# Power.net
KiCad netlist of a schematic drawn in Altium Designer
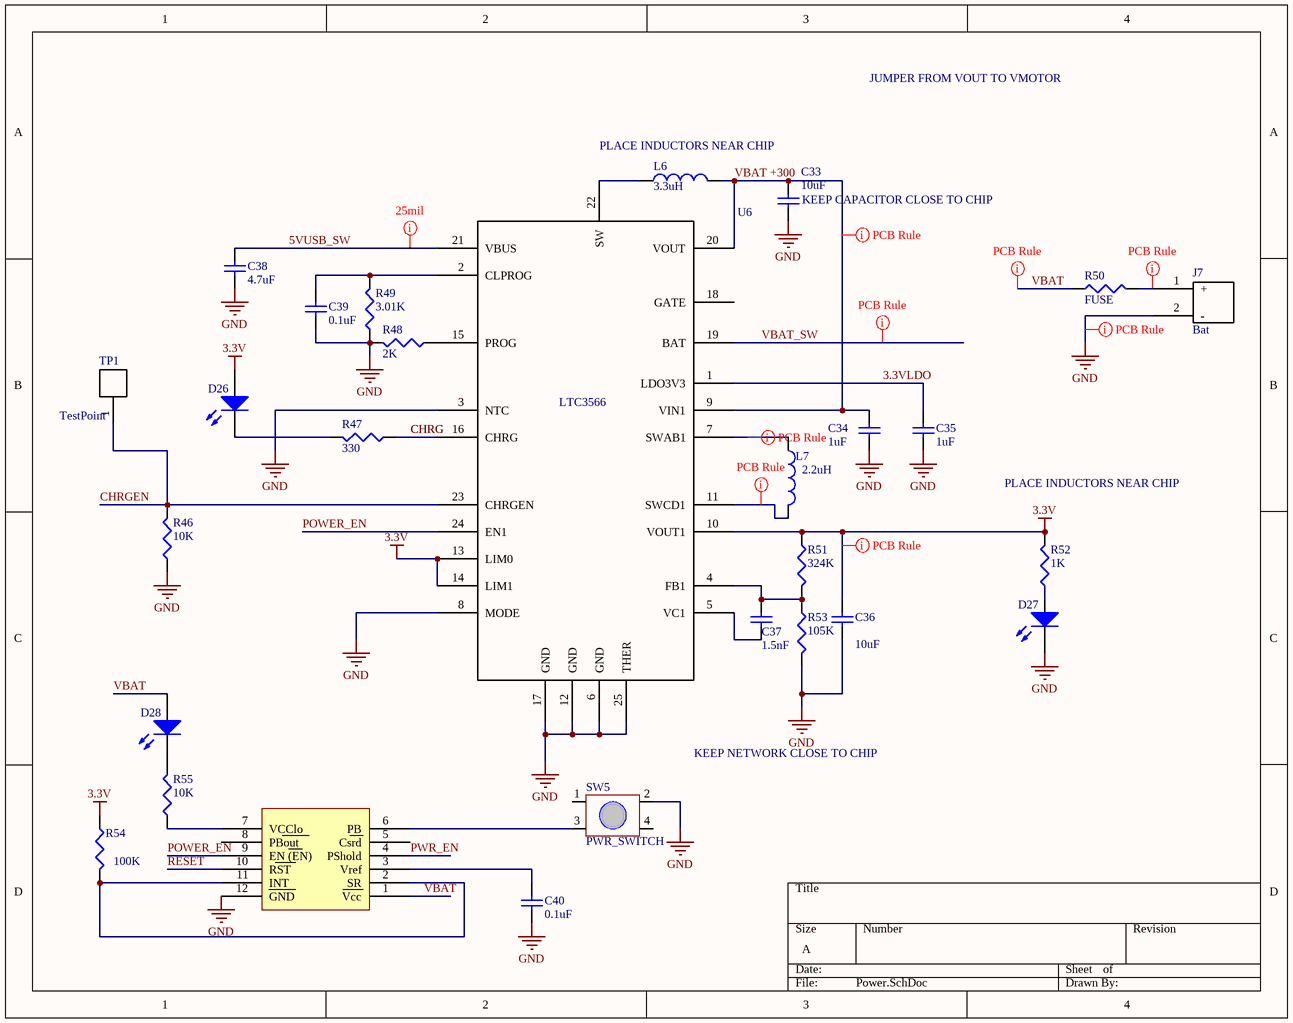
[diagram p0: Power.SchDoc]

(export (version "E")
  (design (tool "Eeschema 10.0.6"))
  (components
    (comp (ref "C33")
      (value "10uF")
      (footprint "CAPC1608L")
      (description "Capacitor")
      (fields (field (name "Comment") "Cap") (field (name "PUBLISHER") "Altium Limited"))
      (libsource (lib "Miscellaneous Devices") (part "Cap"))
    )
    (comp (ref "C34")
      (value "1uF")
      (footprint "CAPC1608L")
      (description "Capacitor")
      (fields (field (name "Comment") "Cap") (field (name "PUBLISHER") "Altium Limited"))
      (libsource (lib "Miscellaneous Devices") (part "Cap"))
    )
    (comp (ref "C35")
      (value "1uF")
      (footprint "CAPC1608L")
      (description "Capacitor")
      (fields (field (name "Comment") "Cap") (field (name "PUBLISHER") "Altium Limited"))
      (libsource (lib "Miscellaneous Devices") (part "Cap"))
    )
    (comp (ref "C36")
      (value "10uF")
      (footprint "CAPC1608L")
      (description "Capacitor")
      (fields (field (name "Comment") "Cap") (field (name "PUBLISHER") "Altium Limited"))
      (libsource (lib "Miscellaneous Devices") (part "Cap"))
    )
    (comp (ref "C37")
      (value "1.5nF")
      (footprint "CAPC1005L")
      (description "Capacitor")
      (fields (field (name "Comment") "Cap") (field (name "PUBLISHER") "Altium Limited"))
      (libsource (lib "Miscellaneous Devices") (part "Cap"))
    )
    (comp (ref "C38")
      (value "4.7uF")
      (footprint "CAPC1608L")
      (description "Capacitor")
      (fields (field (name "Comment") "Cap") (field (name "PUBLISHER") "Altium Limited"))
      (libsource (lib "Miscellaneous Devices") (part "Cap"))
    )
    (comp (ref "C39")
      (value "0.1uF")
      (footprint "CAPC1005L")
      (description "Capacitor")
      (fields (field (name "Comment") "Cap") (field (name "PUBLISHER") "Altium Limited"))
      (libsource (lib "Miscellaneous Devices") (part "Cap"))
    )
    (comp (ref "C40")
      (value "0.1uF")
      (footprint "CAPC1608L")
      (description "Capacitor")
      (fields (field (name "Comment") "Cap") (field (name "PUBLISHER") "Altium Limited"))
      (libsource (lib "Miscellaneous Devices") (part "Cap"))
    )
    (comp (ref "D26")
      (value "Charge")
      (footprint "INDC2012L")
      (description "Typical RED, GREEN, YELLOW, AMBER GaAs LED")
      (fields (field (name "PUBLISHER") "Altium Limited"))
      (libsource (lib "Miscellaneous Devices") (part "LED2"))
    )
    (comp (ref "D27")
      (value "Power")
      (footprint "INDC2012L")
      (description "Typical RED, GREEN, YELLOW, AMBER GaAs LED")
      (fields (field (name "PUBLISHER") "Altium Limited"))
      (libsource (lib "Miscellaneous Devices") (part "LED2"))
    )
    (comp (ref "D28")
      (value "Charge")
      (footprint "INDC2012L")
      (description "Typical RED, GREEN, YELLOW, AMBER GaAs LED")
      (fields (field (name "PUBLISHER") "Altium Limited"))
      (libsource (lib "Miscellaneous Devices") (part "LED2"))
    )
    (comp (ref "J7")
      (value "Bat")
      (footprint "BatteryConnJST")
      (libsource (lib "mrone") (part "BatteryConnJST"))
    )
    (comp (ref "L6") (value "3.3uH") (footprint "IndPow") (libsource (lib "mrone") (part "Inductor")))
    (comp (ref "L7") (value "2.2uH") (footprint "IndPow") (libsource (lib "mrone") (part "Inductor")))
    (comp (ref "R46")
      (value "10K")
      (footprint "RESC1608L")
      (description "Resistor")
      (fields (field (name "Comment") "Res3") (field (name "PUBLISHER") "Altium Limited"))
      (libsource (lib "Miscellaneous Devices") (part "Res3"))
    )
    (comp (ref "R47")
      (value "330")
      (footprint "RESC1608L")
      (description "Resistor")
      (fields (field (name "Comment") "Res3") (field (name "PUBLISHER") "Altium Limited"))
      (libsource (lib "Miscellaneous Devices") (part "Res3"))
    )
    (comp (ref "R48")
      (value "2K")
      (footprint "RESC1608L")
      (description "Resistor")
      (fields (field (name "Comment") "Res3") (field (name "PUBLISHER") "Altium Limited"))
      (libsource (lib "Miscellaneous Devices") (part "Res3"))
    )
    (comp (ref "R49")
      (value "3.01K")
      (footprint "RESC1608L")
      (description "Resistor")
      (fields (field (name "Comment") "Res3") (field (name "PUBLISHER") "Altium Limited"))
      (libsource (lib "Miscellaneous Devices") (part "Res3"))
    )
    (comp (ref "R50")
      (value "FUSE")
      (footprint "RESC3225L")
      (description "Resistor")
      (fields (field (name "Comment") "Res3") (field (name "PUBLISHER") "Altium Limited"))
      (libsource (lib "Miscellaneous Devices") (part "Res3"))
    )
    (comp (ref "R51")
      (value "324K")
      (footprint "RESC1608L")
      (description "Resistor")
      (fields (field (name "Comment") "Res3") (field (name "PUBLISHER") "Altium Limited"))
      (libsource (lib "Miscellaneous Devices") (part "Res3"))
    )
    (comp (ref "R52")
      (value "1K")
      (footprint "RESC1608L")
      (description "Resistor")
      (fields (field (name "Comment") "Res3") (field (name "PUBLISHER") "Altium Limited"))
      (libsource (lib "Miscellaneous Devices") (part "Res3"))
    )
    (comp (ref "R53")
      (value "105K")
      (footprint "RESC1608L")
      (description "Resistor")
      (fields (field (name "Comment") "Res3") (field (name "PUBLISHER") "Altium Limited"))
      (libsource (lib "Miscellaneous Devices") (part "Res3"))
    )
    (comp (ref "R54")
      (value "100K")
      (footprint "RESC1608L")
      (description "Resistor")
      (fields (field (name "Comment") "Res3") (field (name "PUBLISHER") "Altium Limited"))
      (libsource (lib "Miscellaneous Devices") (part "Res3"))
    )
    (comp (ref "R55")
      (value "10K")
      (footprint "RESC1608L")
      (description "Resistor")
      (fields (field (name "Comment") "Res3") (field (name "PUBLISHER") "Altium Limited"))
      (libsource (lib "Miscellaneous Devices") (part "Res3"))
    )
    (comp (ref "SW5")
      (value "PWR_SWITCH")
      (footprint "SwitchTall-TL330")
      (libsource (lib "mrone") (part "Switch-TL330"))
    )
    (comp (ref "TP1")
      (value "TestPoint")
      (footprint "TestPoint")
      (libsource (lib "mrone") (part "TestPoint"))
    )
    (comp (ref "U6")
      (value "LTC3566")
      (footprint "QFN-24")
      (libsource (lib "Schematic Components") (part "LTC3566"))
    )
    (comp (ref "U7") (value "STM6601") (footprint "TDFN12") (libsource (lib "mrone") (part "STM6601")))
  )
  (nets
    (net (code "1") (name "/3.3VLDO") (class "Default")
      (node (ref "C35") (pin "1") (pinfunction "1_1") (pintype "passive"))
      (node (ref "U6") (pin "1") (pinfunction "LDO3V3_1") (pintype "passive"))
    )
    (net (code "2") (name "/5VUSB_SW") (class "Default")
      (node (ref "C38") (pin "2") (pinfunction "2_2") (pintype "passive"))
      (node (ref "U6") (pin "21") (pinfunction "VBUS_21") (pintype "passive"))
    )
    (net (code "3") (name "/CHRG") (class "Default")
      (node (ref "R47") (pin "1") (pinfunction "1_1") (pintype "passive"))
      (node (ref "U6") (pin "16") (pinfunction "CHRG_16") (pintype "passive"))
    )
    (net (code "4") (name "/CHRGEN") (class "Default")
      (node (ref "R46") (pin "2") (pinfunction "2_2") (pintype "passive"))
      (node (ref "TP1") (pin "1") (pintype "passive"))
      (node (ref "U6") (pin "23") (pinfunction "CHRGEN_23") (pintype "passive"))
    )
    (net (code "5") (name "/POWER_EN") (class "Default")
      (node (ref "U6") (pin "24") (pinfunction "EN1_24") (pintype "passive"))
      (node (ref "U7") (pin "9") (pinfunction "EN_(EN)_9") (pintype "passive"))
    )
    (net (code "6") (name "/PWR_EN") (class "Default")
      (node (ref "U7") (pin "4") (pinfunction "PShold_4") (pintype "passive"))
    )
    (net (code "7") (name "/RESET") (class "Default")
      (node (ref "U7") (pin "10") (pinfunction "RST_10") (pintype "passive"))
    )
    (net (code "8") (name "/VBAT") (class "Default")
      (node (ref "D28") (pin "1") (pinfunction "A_1") (pintype "passive"))
      (node (ref "R50") (pin "1") (pinfunction "1_1") (pintype "passive"))
      (node (ref "U7") (pin "1") (pinfunction "Vcc_1") (pintype "open_collector"))
    )
    (net (code "9") (name "/VBAT +300") (class "Default")
      (node (ref "C33") (pin "2") (pinfunction "2_2") (pintype "passive"))
      (node (ref "C34") (pin "1") (pinfunction "1_1") (pintype "passive"))
      (node (ref "L6") (pin "2") (pinfunction "2_2") (pintype "passive"))
      (node (ref "U6") (pin "20") (pinfunction "VOUT_20") (pintype "passive"))
      (node (ref "U6") (pin "9") (pinfunction "VIN1_9") (pintype "passive"))
    )
    (net (code "10") (name "/VBAT_SW") (class "Default")
      (node (ref "U6") (pin "19") (pinfunction "BAT_19") (pintype "passive"))
    )
    (net (code "11") (name "3.3V") (class "Default")
      (node (ref "C36") (pin "2") (pinfunction "2_2") (pintype "passive"))
      (node (ref "D26") (pin "1") (pinfunction "A_1") (pintype "passive"))
      (node (ref "R51") (pin "1") (pinfunction "1_1") (pintype "passive"))
      (node (ref "R52") (pin "2") (pinfunction "2_2") (pintype "passive"))
      (node (ref "R54") (pin "1") (pinfunction "1_1") (pintype "passive"))
      (node (ref "U6") (pin "10") (pinfunction "VOUT1_10") (pintype "passive"))
      (node (ref "U6") (pin "13") (pinfunction "LIM0_13") (pintype "passive"))
      (node (ref "U6") (pin "14") (pinfunction "LIM1_14") (pintype "passive"))
    )
    (net (code "12") (name "GND") (class "Default")
      (node (ref "C33") (pin "1") (pinfunction "1_1") (pintype "passive"))
      (node (ref "C34") (pin "2") (pinfunction "2_2") (pintype "passive"))
      (node (ref "C35") (pin "2") (pinfunction "2_2") (pintype "passive"))
      (node (ref "C36") (pin "1") (pinfunction "1_1") (pintype "passive"))
      (node (ref "C38") (pin "1") (pinfunction "1_1") (pintype "passive"))
      (node (ref "C39") (pin "1") (pinfunction "1_1") (pintype "passive"))
      (node (ref "C40") (pin "1") (pinfunction "1_1") (pintype "passive"))
      (node (ref "D27") (pin "2") (pinfunction "K_2") (pintype "passive"))
      (node (ref "J7") (pin "2") (pinfunction "-_2") (pintype "passive"))
      (node (ref "R46") (pin "1") (pinfunction "1_1") (pintype "passive"))
      (node (ref "R48") (pin "2") (pinfunction "2_2") (pintype "passive"))
      (node (ref "R49") (pin "1") (pinfunction "1_1") (pintype "passive"))
      (node (ref "R53") (pin "2") (pinfunction "2_2") (pintype "passive"))
      (node (ref "SW5") (pin "2") (pinfunction "2_2") (pintype "passive"))
      (node (ref "U6") (pin "12") (pinfunction "GND_12") (pintype "passive"))
      (node (ref "U6") (pin "17") (pinfunction "GND_17") (pintype "passive"))
      (node (ref "U6") (pin "25") (pinfunction "THER_25") (pintype "passive"))
      (node (ref "U6") (pin "3") (pinfunction "NTC_3") (pintype "passive"))
      (node (ref "U6") (pin "6") (pinfunction "GND_6") (pintype "passive"))
      (node (ref "U6") (pin "8") (pinfunction "MODE_8") (pintype "passive"))
      (node (ref "U7") (pin "12") (pinfunction "GND_12") (pintype "passive"))
    )
    (net (code "13") (name "Net-(D26-K)") (class "Default")
      (node (ref "D26") (pin "2") (pinfunction "K_2") (pintype "passive"))
      (node (ref "R47") (pin "2") (pinfunction "2_2") (pintype "passive"))
    )
    (net (code "14") (name "Net-(D27-A)") (class "Default")
      (node (ref "D27") (pin "1") (pinfunction "A_1") (pintype "passive"))
      (node (ref "R52") (pin "1") (pinfunction "1_1") (pintype "passive"))
    )
    (net (code "15") (name "Net-(D28-K)") (class "Default")
      (node (ref "D28") (pin "2") (pinfunction "K_2") (pintype "passive"))
      (node (ref "R55") (pin "2") (pinfunction "2_2") (pintype "passive"))
    )
    (net (code "16") (name "Net-(J7-+)") (class "Default")
      (node (ref "J7") (pin "1") (pinfunction "+_1") (pintype "passive"))
      (node (ref "R50") (pin "2") (pinfunction "2_2") (pintype "passive"))
    )
    (net (code "17") (name "Net-(U6-CLPROG)") (class "Default")
      (node (ref "C39") (pin "2") (pinfunction "2_2") (pintype "passive"))
      (node (ref "R49") (pin "2") (pinfunction "2_2") (pintype "passive"))
      (node (ref "U6") (pin "2") (pinfunction "CLPROG_2") (pintype "passive"))
    )
    (net (code "18") (name "Net-(U6-FB1)") (class "Default")
      (node (ref "C37") (pin "1") (pinfunction "1_1") (pintype "passive"))
      (node (ref "R51") (pin "2") (pinfunction "2_2") (pintype "passive"))
      (node (ref "R53") (pin "1") (pinfunction "1_1") (pintype "passive"))
      (node (ref "U6") (pin "4") (pinfunction "FB1_4") (pintype "passive"))
    )
    (net (code "19") (name "Net-(U6-PROG)") (class "Default")
      (node (ref "R48") (pin "1") (pinfunction "1_1") (pintype "passive"))
      (node (ref "U6") (pin "15") (pinfunction "PROG_15") (pintype "passive"))
    )
    (net (code "20") (name "Net-(U6-SW)") (class "Default")
      (node (ref "L6") (pin "1") (pinfunction "1_1") (pintype "passive"))
      (node (ref "U6") (pin "22") (pinfunction "SW_22") (pintype "passive"))
    )
    (net (code "21") (name "Net-(U6-SWAB1)") (class "Default")
      (node (ref "L7") (pin "1") (pinfunction "1_1") (pintype "passive"))
      (node (ref "U6") (pin "7") (pinfunction "SWAB1_7") (pintype "passive"))
    )
    (net (code "22") (name "Net-(U6-SWCD1)") (class "Default")
      (node (ref "L7") (pin "2") (pinfunction "2_2") (pintype "passive"))
      (node (ref "U6") (pin "11") (pinfunction "SWCD1_11") (pintype "passive"))
    )
    (net (code "23") (name "Net-(U6-VC1)") (class "Default")
      (node (ref "C37") (pin "2") (pinfunction "2_2") (pintype "passive"))
      (node (ref "U6") (pin "5") (pinfunction "VC1_5") (pintype "passive"))
    )
    (net (code "24") (name "Net-(U7-INT)") (class "Default")
      (node (ref "R54") (pin "2") (pinfunction "2_2") (pintype "passive"))
      (node (ref "U7") (pin "11") (pinfunction "INT_11") (pintype "passive"))
      (node (ref "U7") (pin "2") (pinfunction "SR_2") (pintype "passive"))
    )
    (net (code "25") (name "Net-(U7-PB)") (class "Default")
      (node (ref "SW5") (pin "3") (pinfunction "3_3") (pintype "passive"))
      (node (ref "U7") (pin "6") (pinfunction "PB_6") (pintype "passive"))
    )
    (net (code "26") (name "Net-(U7-VCClo)") (class "Default")
      (node (ref "R55") (pin "1") (pinfunction "1_1") (pintype "passive"))
      (node (ref "U7") (pin "7") (pinfunction "VCClo_7") (pintype "passive"))
    )
    (net (code "27") (name "Net-(U7-Vref)") (class "Default")
      (node (ref "C40") (pin "2") (pinfunction "2_2") (pintype "passive"))
      (node (ref "U7") (pin "3") (pinfunction "Vref_3") (pintype "passive"))
    )
    (net (code "28") (name "unconnected-(SW5-Pad1)") (class "Default")
      (node (ref "SW5") (pin "1") (pinfunction "1_1") (pintype "passive"))
    )
    (net (code "29") (name "unconnected-(SW5-Pad4)") (class "Default")
      (node (ref "SW5") (pin "4") (pinfunction "4_4") (pintype "passive"))
    )
    (net (code "30") (name "unconnected-(U6-GATE-Pad18)") (class "Default")
      (node (ref "U6") (pin "18") (pinfunction "GATE_18") (pintype "passive"))
    )
    (net (code "31") (name "unconnected-(U7-Csrd-Pad5)") (class "Default")
      (node (ref "U7") (pin "5") (pinfunction "Csrd_5") (pintype "passive"))
    )
    (net (code "32") (name "unconnected-(U7-PBout-Pad8)") (class "Default")
      (node (ref "U7") (pin "8") (pinfunction "PBout_8") (pintype "passive"))
    )
  )
)
